# 2_4_x3.net
KiCad netlist of a schematic drawn in Altium Designer
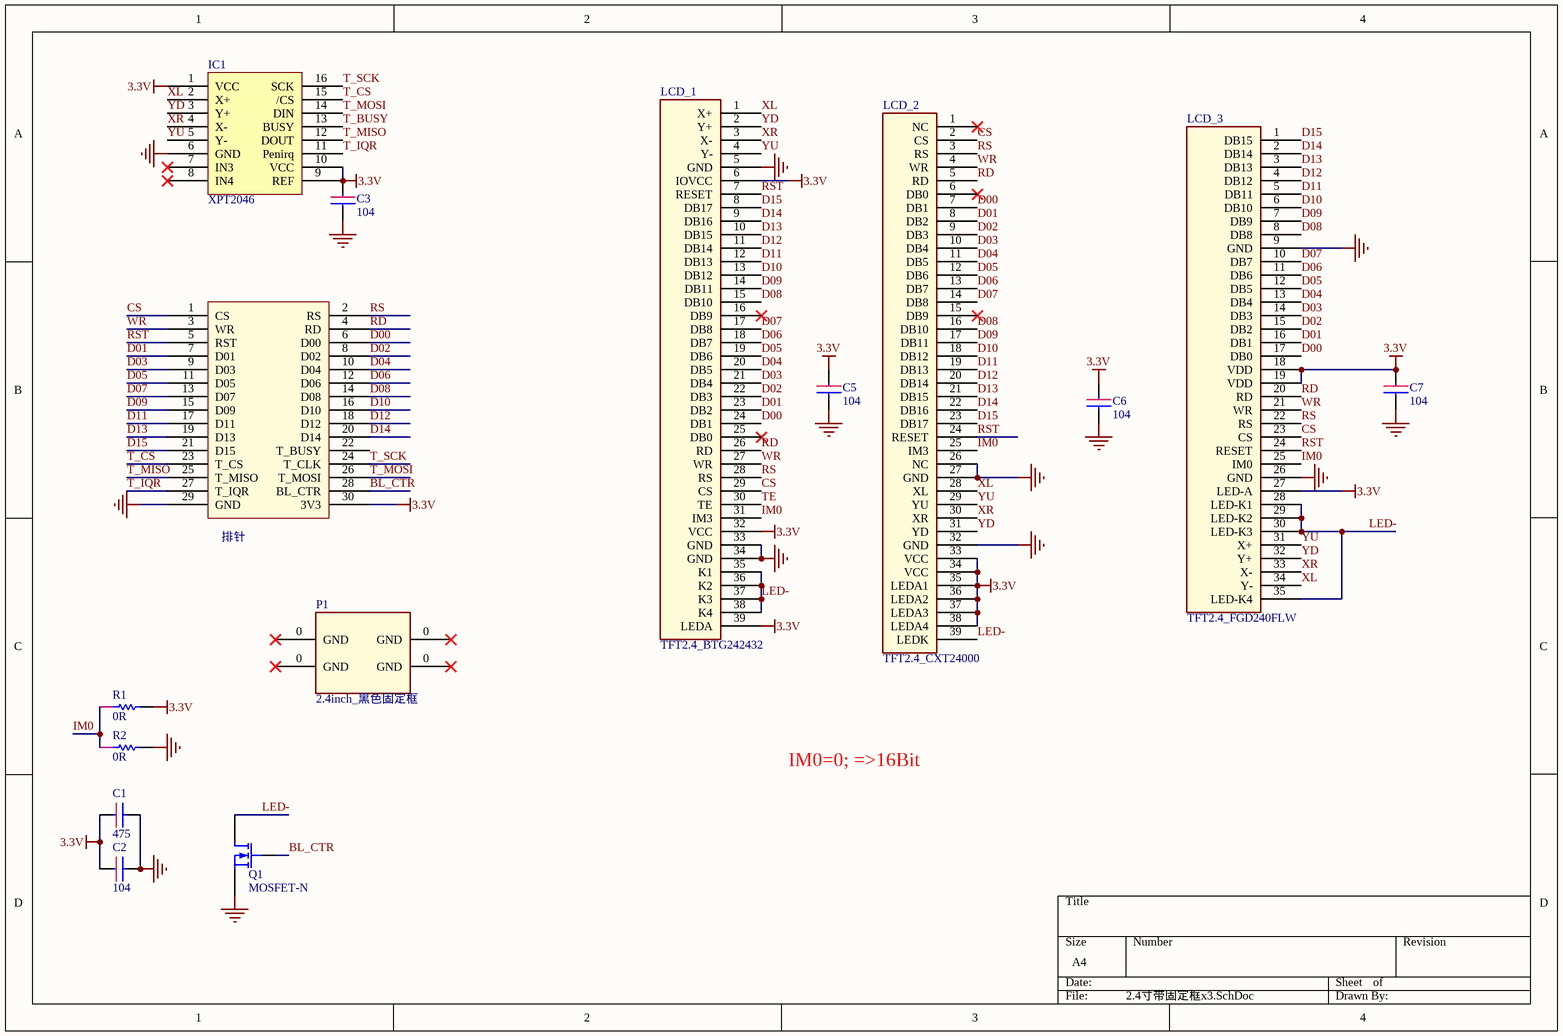
[diagram p0: 2.4寸带固定框x3.SchDoc]

(export (version "E")
  (design (tool "Eeschema 10.0.6"))
  (components
    (comp (ref "C1") (value "475") (footprint "C0603-2") (libsource (lib "Tiky") (part "cap")))
    (comp (ref "C2") (value "104") (footprint "C0603-1") (libsource (lib "Tiky") (part "cap")))
    (comp (ref "C3") (value "104") (footprint "C0603-2") (libsource (lib "Tiky") (part "cap")))
    (comp (ref "C5") (value "104") (footprint "C0603-1") (libsource (lib "Tiky") (part "cap")))
    (comp (ref "C6") (value "104") (footprint "C0603-1") (libsource (lib "Tiky") (part "cap")))
    (comp (ref "C7") (value "104") (footprint "C0603-1") (libsource (lib "Tiky") (part "cap")))
    (comp (ref "IC1") (value "XPT2046") (footprint "SOT403-1") (libsource (lib "Tiky") (part "ADS7843")))
    (comp (ref "LCD_1")
      (value "TFT2.4_BTG242432")
      (footprint "TFT2.4_BTG242432")
      (libsource (lib "Tiky") (part "TFT2.4_BTG242432"))
    )
    (comp (ref "LCD_2")
      (value "TFT2.4_CXT24000")
      (footprint "TFT2.4_CXT24000")
      (libsource (lib "Tiky") (part "TFT2.4_CXT24000"))
    )
    (comp (ref "LCD_3")
      (value "TFT2.4_FGD240FLW")
      (footprint "TFT2.4_FGD240FLW")
      (libsource (lib "Tiky") (part "TFT2.4_FGD240FLW"))
    )
    (comp (ref "P1")
      (value "2.4inch_黑色固定框")
      (footprint "2.4inch_黑色固定框")
      (libsource (lib "Tiky") (part "2.4inch_黑色固定框"))
    )
    (comp (ref "Q1") (value "MOSFET-N") (footprint "SOT23A") (libsource (lib "Tiky") (part "MOSFET-N")))
    (comp (ref "R1") (value "0R") (footprint "R0603") (libsource (lib "Tiky") (part "Resistor")))
    (comp (ref "R2") (value "0R") (footprint "R0603") (libsource (lib "Tiky") (part "Resistor")))
    (comp (ref "公认通用") (value "排针") (footprint "P_Head_2x15") (libsource (lib "Tiky") (part "LCD_common")))
  )
  (nets
    (net (code "1") (name "/BL_CTR") (class "Default")
      (node (ref "Q1") (pin "1") (pinfunction "G_1") (pintype "passive"))
      (node (ref "公认通用") (pin "28") (pinfunction "BL_CTR_28") (pintype "passive"))
    )
    (net (code "2") (name "/CS") (class "Default")
      (node (ref "LCD_1") (pin "29") (pinfunction "CS_29") (pintype "passive"))
      (node (ref "LCD_2") (pin "2") (pinfunction "CS_2") (pintype "passive"))
      (node (ref "LCD_3") (pin "23") (pinfunction "CS_23") (pintype "passive"))
      (node (ref "公认通用") (pin "1") (pinfunction "CS_1") (pintype "passive"))
    )
    (net (code "3") (name "/D00") (class "Default")
      (node (ref "LCD_1") (pin "24") (pinfunction "DB1_24") (pintype "passive"))
      (node (ref "LCD_2") (pin "7") (pinfunction "DB1_7") (pintype "passive"))
      (node (ref "LCD_3") (pin "17") (pinfunction "DB0_17") (pintype "passive"))
      (node (ref "公认通用") (pin "6") (pinfunction "D00_6") (pintype "passive"))
    )
    (net (code "4") (name "/D01") (class "Default")
      (node (ref "LCD_1") (pin "23") (pinfunction "DB2_23") (pintype "passive"))
      (node (ref "LCD_2") (pin "8") (pinfunction "DB2_8") (pintype "passive"))
      (node (ref "LCD_3") (pin "16") (pinfunction "DB1_16") (pintype "passive"))
      (node (ref "公认通用") (pin "7") (pinfunction "D01_7") (pintype "passive"))
    )
    (net (code "5") (name "/D02") (class "Default")
      (node (ref "LCD_1") (pin "22") (pinfunction "DB3_22") (pintype "passive"))
      (node (ref "LCD_2") (pin "9") (pinfunction "DB3_9") (pintype "passive"))
      (node (ref "LCD_3") (pin "15") (pinfunction "DB2_15") (pintype "passive"))
      (node (ref "公认通用") (pin "8") (pinfunction "D02_8") (pintype "passive"))
    )
    (net (code "6") (name "/D03") (class "Default")
      (node (ref "LCD_1") (pin "21") (pinfunction "DB4_21") (pintype "passive"))
      (node (ref "LCD_2") (pin "10") (pinfunction "DB4_10") (pintype "passive"))
      (node (ref "LCD_3") (pin "14") (pinfunction "DB3_14") (pintype "passive"))
      (node (ref "公认通用") (pin "9") (pinfunction "D03_9") (pintype "passive"))
    )
    (net (code "7") (name "/D04") (class "Default")
      (node (ref "LCD_1") (pin "20") (pinfunction "DB5_20") (pintype "passive"))
      (node (ref "LCD_2") (pin "11") (pinfunction "DB5_11") (pintype "passive"))
      (node (ref "LCD_3") (pin "13") (pinfunction "DB4_13") (pintype "passive"))
      (node (ref "公认通用") (pin "10") (pinfunction "D04_10") (pintype "passive"))
    )
    (net (code "8") (name "/D05") (class "Default")
      (node (ref "LCD_1") (pin "19") (pinfunction "DB6_19") (pintype "passive"))
      (node (ref "LCD_2") (pin "12") (pinfunction "DB6_12") (pintype "passive"))
      (node (ref "LCD_3") (pin "12") (pinfunction "DB5_12") (pintype "passive"))
      (node (ref "公认通用") (pin "11") (pinfunction "D05_11") (pintype "passive"))
    )
    (net (code "9") (name "/D06") (class "Default")
      (node (ref "LCD_1") (pin "18") (pinfunction "DB7_18") (pintype "passive"))
      (node (ref "LCD_2") (pin "13") (pinfunction "DB7_13") (pintype "passive"))
      (node (ref "LCD_3") (pin "11") (pinfunction "DB6_11") (pintype "passive"))
      (node (ref "公认通用") (pin "12") (pinfunction "D06_12") (pintype "passive"))
    )
    (net (code "10") (name "/D07") (class "Default")
      (node (ref "LCD_1") (pin "17") (pinfunction "DB8_17") (pintype "passive"))
      (node (ref "LCD_2") (pin "14") (pinfunction "DB8_14") (pintype "passive"))
      (node (ref "LCD_3") (pin "10") (pinfunction "DB7_10") (pintype "passive"))
      (node (ref "公认通用") (pin "13") (pinfunction "D07_13") (pintype "passive"))
    )
    (net (code "11") (name "/D08") (class "Default")
      (node (ref "LCD_1") (pin "15") (pinfunction "DB10_15") (pintype "passive"))
      (node (ref "LCD_2") (pin "16") (pinfunction "DB10_16") (pintype "passive"))
      (node (ref "LCD_3") (pin "8") (pinfunction "DB8_8") (pintype "passive"))
      (node (ref "公认通用") (pin "14") (pinfunction "D08_14") (pintype "passive"))
    )
    (net (code "12") (name "/D09") (class "Default")
      (node (ref "LCD_1") (pin "14") (pinfunction "DB11_14") (pintype "passive"))
      (node (ref "LCD_2") (pin "17") (pinfunction "DB11_17") (pintype "passive"))
      (node (ref "LCD_3") (pin "7") (pinfunction "DB9_7") (pintype "passive"))
      (node (ref "公认通用") (pin "15") (pinfunction "D09_15") (pintype "passive"))
    )
    (net (code "13") (name "/D10") (class "Default")
      (node (ref "LCD_1") (pin "13") (pinfunction "DB12_13") (pintype "passive"))
      (node (ref "LCD_2") (pin "18") (pinfunction "DB12_18") (pintype "passive"))
      (node (ref "LCD_3") (pin "6") (pinfunction "DB10_6") (pintype "passive"))
      (node (ref "公认通用") (pin "16") (pinfunction "D10_16") (pintype "passive"))
    )
    (net (code "14") (name "/D11") (class "Default")
      (node (ref "LCD_1") (pin "12") (pinfunction "DB13_12") (pintype "passive"))
      (node (ref "LCD_2") (pin "19") (pinfunction "DB13_19") (pintype "passive"))
      (node (ref "LCD_3") (pin "5") (pinfunction "DB11_5") (pintype "passive"))
      (node (ref "公认通用") (pin "17") (pinfunction "D11_17") (pintype "passive"))
    )
    (net (code "15") (name "/D12") (class "Default")
      (node (ref "LCD_1") (pin "11") (pinfunction "DB14_11") (pintype "passive"))
      (node (ref "LCD_2") (pin "20") (pinfunction "DB14_20") (pintype "passive"))
      (node (ref "LCD_3") (pin "4") (pinfunction "DB12_4") (pintype "passive"))
      (node (ref "公认通用") (pin "18") (pinfunction "D12_18") (pintype "passive"))
    )
    (net (code "16") (name "/D13") (class "Default")
      (node (ref "LCD_1") (pin "10") (pinfunction "DB15_10") (pintype "passive"))
      (node (ref "LCD_2") (pin "21") (pinfunction "DB15_21") (pintype "passive"))
      (node (ref "LCD_3") (pin "3") (pinfunction "DB13_3") (pintype "passive"))
      (node (ref "公认通用") (pin "19") (pinfunction "D13_19") (pintype "passive"))
    )
    (net (code "17") (name "/D14") (class "Default")
      (node (ref "LCD_1") (pin "9") (pinfunction "DB16_9") (pintype "passive"))
      (node (ref "LCD_2") (pin "22") (pinfunction "DB16_22") (pintype "passive"))
      (node (ref "LCD_3") (pin "2") (pinfunction "DB14_2") (pintype "passive"))
      (node (ref "公认通用") (pin "20") (pinfunction "D14_20") (pintype "passive"))
    )
    (net (code "18") (name "/D15") (class "Default")
      (node (ref "LCD_1") (pin "8") (pinfunction "DB17_8") (pintype "passive"))
      (node (ref "LCD_2") (pin "23") (pinfunction "DB17_23") (pintype "passive"))
      (node (ref "LCD_3") (pin "1") (pinfunction "DB15_1") (pintype "passive"))
      (node (ref "公认通用") (pin "21") (pinfunction "D15_21") (pintype "passive"))
    )
    (net (code "19") (name "/IM0") (class "Default")
      (node (ref "LCD_1") (pin "31") (pinfunction "IM3_31") (pintype "passive"))
      (node (ref "LCD_2") (pin "25") (pinfunction "IM3_25") (pintype "passive"))
      (node (ref "LCD_3") (pin "25") (pinfunction "IM0_25") (pintype "passive"))
      (node (ref "R1") (pin "1") (pinfunction "1_1") (pintype "passive"))
      (node (ref "R2") (pin "1") (pinfunction "1_1") (pintype "passive"))
    )
    (net (code "20") (name "/LED-") (class "Default")
      (node (ref "LCD_1") (pin "35") (pinfunction "K1_35") (pintype "passive"))
      (node (ref "LCD_1") (pin "36") (pinfunction "K2_36") (pintype "passive"))
      (node (ref "LCD_1") (pin "37") (pinfunction "K3_37") (pintype "passive"))
      (node (ref "LCD_1") (pin "38") (pinfunction "K4_38") (pintype "passive"))
      (node (ref "LCD_2") (pin "39") (pinfunction "LEDK_39") (pintype "passive"))
      (node (ref "LCD_3") (pin "28") (pinfunction "LED-K1_28") (pintype "passive"))
      (node (ref "LCD_3") (pin "29") (pinfunction "LED-K2_29") (pintype "passive"))
      (node (ref "LCD_3") (pin "30") (pinfunction "LED-K3_30") (pintype "passive"))
      (node (ref "LCD_3") (pin "35") (pinfunction "LED-K4_35") (pintype "passive"))
      (node (ref "Q1") (pin "3") (pinfunction "D_3") (pintype "passive"))
    )
    (net (code "21") (name "/RD") (class "Default")
      (node (ref "LCD_1") (pin "26") (pinfunction "RD_26") (pintype "passive"))
      (node (ref "LCD_2") (pin "5") (pinfunction "RD_5") (pintype "passive"))
      (node (ref "LCD_3") (pin "20") (pinfunction "RD_20") (pintype "passive"))
      (node (ref "公认通用") (pin "4") (pinfunction "RD_4") (pintype "passive"))
    )
    (net (code "22") (name "/RS") (class "Default")
      (node (ref "LCD_1") (pin "28") (pinfunction "RS_28") (pintype "passive"))
      (node (ref "LCD_2") (pin "3") (pinfunction "RS_3") (pintype "passive"))
      (node (ref "LCD_3") (pin "22") (pinfunction "RS_22") (pintype "passive"))
      (node (ref "公认通用") (pin "2") (pinfunction "RS_2") (pintype "passive"))
    )
    (net (code "23") (name "/RST") (class "Default")
      (node (ref "LCD_1") (pin "7") (pinfunction "RESET_7") (pintype "passive"))
      (node (ref "LCD_2") (pin "24") (pinfunction "RESET_24") (pintype "passive"))
      (node (ref "LCD_3") (pin "24") (pinfunction "RESET_24") (pintype "passive"))
      (node (ref "公认通用") (pin "5") (pinfunction "RST_5") (pintype "passive"))
    )
    (net (code "24") (name "/TE") (class "Default")
      (node (ref "LCD_1") (pin "30") (pinfunction "TE_30") (pintype "passive"))
    )
    (net (code "25") (name "/T_BUSY") (class "Default")
      (node (ref "IC1") (pin "13") (pinfunction "BUSY_13") (pintype "passive"))
    )
    (net (code "26") (name "/T_CS") (class "Default")
      (node (ref "IC1") (pin "15") (pinfunction "/CS_15") (pintype "passive"))
      (node (ref "公认通用") (pin "23") (pinfunction "T_CS_23") (pintype "passive"))
    )
    (net (code "27") (name "/T_IQR") (class "Default")
      (node (ref "IC1") (pin "11") (pinfunction "Penirq_11") (pintype "passive"))
      (node (ref "公认通用") (pin "27") (pinfunction "T_IQR_27") (pintype "passive"))
    )
    (net (code "28") (name "/T_MISO") (class "Default")
      (node (ref "IC1") (pin "12") (pinfunction "DOUT_12") (pintype "passive"))
      (node (ref "公认通用") (pin "25") (pinfunction "T_MISO_25") (pintype "passive"))
    )
    (net (code "29") (name "/T_MOSI") (class "Default")
      (node (ref "IC1") (pin "14") (pinfunction "DIN_14") (pintype "passive"))
      (node (ref "公认通用") (pin "26") (pinfunction "T_MOSI_26") (pintype "passive"))
    )
    (net (code "30") (name "/T_SCK") (class "Default")
      (node (ref "IC1") (pin "16") (pinfunction "SCK_16") (pintype "passive"))
      (node (ref "公认通用") (pin "24") (pinfunction "T_CLK_24") (pintype "passive"))
    )
    (net (code "31") (name "/WR") (class "Default")
      (node (ref "LCD_1") (pin "27") (pinfunction "WR_27") (pintype "passive"))
      (node (ref "LCD_2") (pin "4") (pinfunction "WR_4") (pintype "passive"))
      (node (ref "LCD_3") (pin "21") (pinfunction "WR_21") (pintype "passive"))
      (node (ref "公认通用") (pin "3") (pinfunction "WR_3") (pintype "passive"))
    )
    (net (code "32") (name "/XL") (class "Default")
      (node (ref "IC1") (pin "2") (pinfunction "X+_2") (pintype "passive"))
      (node (ref "LCD_1") (pin "1") (pinfunction "X+_1") (pintype "passive"))
      (node (ref "LCD_2") (pin "28") (pinfunction "XL_28") (pintype "passive"))
      (node (ref "LCD_3") (pin "34") (pinfunction "Y-_34") (pintype "passive"))
    )
    (net (code "33") (name "/XR") (class "Default")
      (node (ref "IC1") (pin "4") (pinfunction "X-_4") (pintype "passive"))
      (node (ref "LCD_1") (pin "3") (pinfunction "X-_3") (pintype "passive"))
      (node (ref "LCD_2") (pin "30") (pinfunction "XR_30") (pintype "passive"))
      (node (ref "LCD_3") (pin "33") (pinfunction "X-_33") (pintype "passive"))
    )
    (net (code "34") (name "/YD") (class "Default")
      (node (ref "IC1") (pin "3") (pinfunction "Y+_3") (pintype "passive"))
      (node (ref "LCD_1") (pin "2") (pinfunction "Y+_2") (pintype "passive"))
      (node (ref "LCD_2") (pin "31") (pinfunction "YD_31") (pintype "passive"))
      (node (ref "LCD_3") (pin "32") (pinfunction "Y+_32") (pintype "passive"))
    )
    (net (code "35") (name "/YU") (class "Default")
      (node (ref "IC1") (pin "5") (pinfunction "Y-_5") (pintype "passive"))
      (node (ref "LCD_1") (pin "4") (pinfunction "Y-_4") (pintype "passive"))
      (node (ref "LCD_2") (pin "29") (pinfunction "YU_29") (pintype "passive"))
      (node (ref "LCD_3") (pin "31") (pinfunction "X+_31") (pintype "passive"))
    )
    (net (code "36") (name "3.3V") (class "Default")
      (node (ref "C1") (pin "1") (pinfunction "1_1") (pintype "passive"))
      (node (ref "C2") (pin "1") (pinfunction "1_1") (pintype "passive"))
      (node (ref "C3") (pin "1") (pinfunction "1_1") (pintype "passive"))
      (node (ref "C5") (pin "1") (pinfunction "1_1") (pintype "passive"))
      (node (ref "C6") (pin "1") (pinfunction "1_1") (pintype "passive"))
      (node (ref "C7") (pin "1") (pinfunction "1_1") (pintype "passive"))
      (node (ref "IC1") (pin "1") (pinfunction "VCC_1") (pintype "passive"))
      (node (ref "IC1") (pin "10") (pinfunction "VCC_10") (pintype "passive"))
      (node (ref "IC1") (pin "9") (pinfunction "REF_9") (pintype "passive"))
      (node (ref "LCD_1") (pin "32") (pinfunction "VCC_32") (pintype "passive"))
      (node (ref "LCD_1") (pin "39") (pinfunction "LEDA_39") (pintype "passive"))
      (node (ref "LCD_1") (pin "6") (pinfunction "IOVCC_6") (pintype "passive"))
      (node (ref "LCD_2") (pin "33") (pinfunction "VCC_33") (pintype "passive"))
      (node (ref "LCD_2") (pin "34") (pinfunction "VCC_34") (pintype "passive"))
      (node (ref "LCD_2") (pin "35") (pinfunction "LEDA1_35") (pintype "passive"))
      (node (ref "LCD_2") (pin "36") (pinfunction "LEDA2_36") (pintype "passive"))
      (node (ref "LCD_2") (pin "37") (pinfunction "LEDA3_37") (pintype "passive"))
      (node (ref "LCD_2") (pin "38") (pinfunction "LEDA4_38") (pintype "passive"))
      (node (ref "LCD_3") (pin "18") (pinfunction "VDD_18") (pintype "passive"))
      (node (ref "LCD_3") (pin "19") (pinfunction "VDD_19") (pintype "passive"))
      (node (ref "LCD_3") (pin "27") (pinfunction "LED-A_27") (pintype "passive"))
      (node (ref "R1") (pin "2") (pinfunction "2_2") (pintype "passive"))
      (node (ref "公认通用") (pin "30") (pinfunction "3V3_30") (pintype "passive"))
    )
    (net (code "37") (name "GND") (class "Default")
      (node (ref "C1") (pin "2") (pinfunction "2_2") (pintype "passive"))
      (node (ref "C2") (pin "2") (pinfunction "2_2") (pintype "passive"))
      (node (ref "C3") (pin "2") (pinfunction "2_2") (pintype "passive"))
      (node (ref "C5") (pin "2") (pinfunction "2_2") (pintype "passive"))
      (node (ref "C6") (pin "2") (pinfunction "2_2") (pintype "passive"))
      (node (ref "C7") (pin "2") (pinfunction "2_2") (pintype "passive"))
      (node (ref "IC1") (pin "6") (pinfunction "GND_6") (pintype "passive"))
      (node (ref "LCD_1") (pin "33") (pinfunction "GND_33") (pintype "passive"))
      (node (ref "LCD_1") (pin "34") (pinfunction "GND_34") (pintype "passive"))
      (node (ref "LCD_1") (pin "5") (pinfunction "GND_5") (pintype "passive"))
      (node (ref "LCD_2") (pin "26") (pinfunction "NC_26") (pintype "passive"))
      (node (ref "LCD_2") (pin "27") (pinfunction "GND_27") (pintype "passive"))
      (node (ref "LCD_2") (pin "32") (pinfunction "GND_32") (pintype "passive"))
      (node (ref "LCD_3") (pin "26") (pinfunction "GND_26") (pintype "passive"))
      (node (ref "LCD_3") (pin "9") (pinfunction "GND_9") (pintype "passive"))
      (node (ref "Q1") (pin "2") (pinfunction "S_2") (pintype "passive"))
      (node (ref "R2") (pin "2") (pinfunction "2_2") (pintype "passive"))
      (node (ref "公认通用") (pin "29") (pinfunction "GND_29") (pintype "passive"))
    )
    (net (code "38") (name "unconnected-(IC1-IN3-Pad7)") (class "Default")
      (node (ref "IC1") (pin "7") (pinfunction "IN3_7") (pintype "passive+no_connect"))
    )
    (net (code "39") (name "unconnected-(IC1-IN4-Pad8)") (class "Default")
      (node (ref "IC1") (pin "8") (pinfunction "IN4_8") (pintype "passive+no_connect"))
    )
    (net (code "40") (name "unconnected-(LCD_1-DB0-Pad25)") (class "Default")
      (node (ref "LCD_1") (pin "25") (pinfunction "DB0_25") (pintype "passive+no_connect"))
    )
    (net (code "41") (name "unconnected-(LCD_1-DB9-Pad16)") (class "Default")
      (node (ref "LCD_1") (pin "16") (pinfunction "DB9_16") (pintype "passive+no_connect"))
    )
    (net (code "42") (name "unconnected-(LCD_2-DB0-Pad6)") (class "Default")
      (node (ref "LCD_2") (pin "6") (pinfunction "DB0_6") (pintype "passive+no_connect"))
    )
    (net (code "43") (name "unconnected-(LCD_2-DB9-Pad15)") (class "Default")
      (node (ref "LCD_2") (pin "15") (pinfunction "DB9_15") (pintype "passive+no_connect"))
    )
    (net (code "44") (name "unconnected-(LCD_2-NC-Pad1)") (class "Default")
      (node (ref "LCD_2") (pin "1") (pinfunction "NC_1") (pintype "passive+no_connect"))
    )
    (net (code "45") (name "unconnected-(P1-GND-Pad0)") (class "Default")
      (node (ref "P1") (pin "0") (pinfunction "GND_0") (pintype "passive+no_connect"))
    )
    (net (code "46") (name "unconnected-(P1-GND-Pad0)_1") (class "Default")
      (node (ref "P1") (pin "0") (pinfunction "GND_0") (pintype "passive+no_connect"))
    )
    (net (code "47") (name "unconnected-(P1-GND-Pad0)_2") (class "Default")
      (node (ref "P1") (pin "0") (pinfunction "GND_0") (pintype "passive+no_connect"))
    )
    (net (code "48") (name "unconnected-(P1-GND-Pad0)_3") (class "Default")
      (node (ref "P1") (pin "0") (pinfunction "GND_0") (pintype "passive+no_connect"))
    )
    (net (code "49") (name "unconnected-(公认通用-T_BUSY-Pad22)") (class "Default")
      (node (ref "公认通用") (pin "22") (pinfunction "T_BUSY_22") (pintype "passive"))
    )
  )
)
